# Multi2Meter.net
KiCad netlist of a schematic drawn in Altium Designer
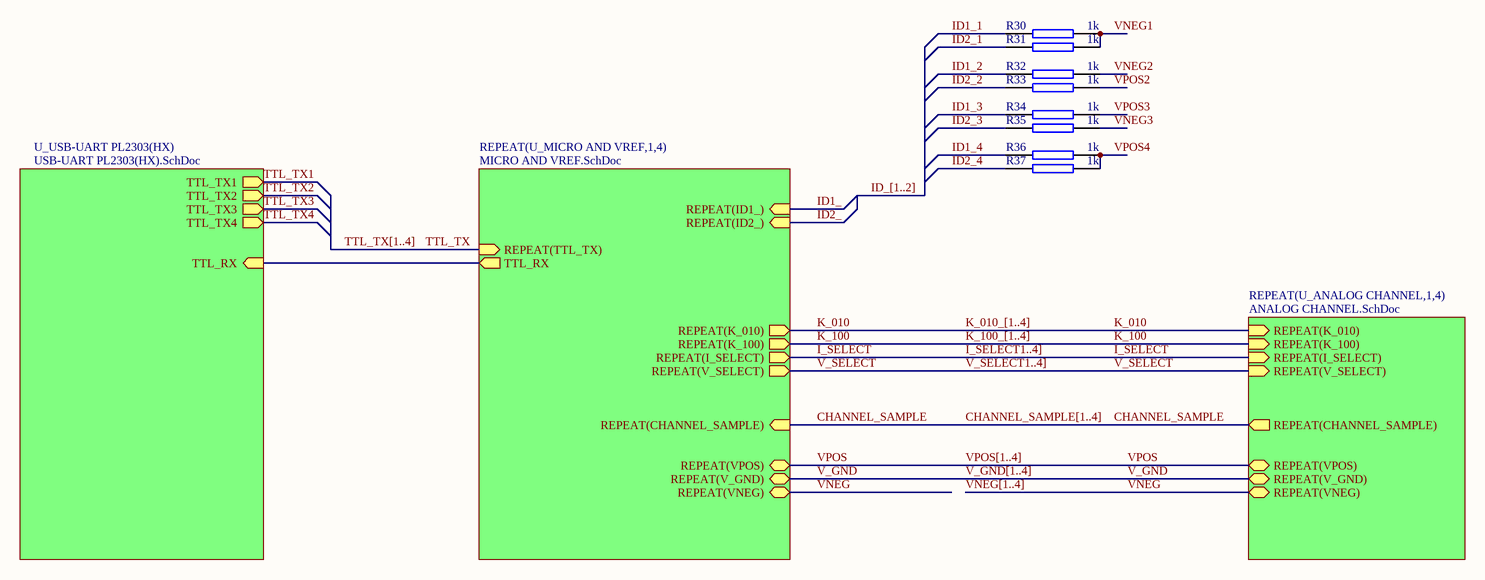
[diagram p0: Multi2Meter.SchDoc]

(export (version "E")
  (design (tool "Eeschema 10.0.6"))
  (components
    (comp (ref "R30")
      (value "1k")
      (footprint "RES (3D) - 0603")
      (description "RESISTOR SMD 0603")
      (libsource (lib "NASCO") (part "RES SMD 0603"))
    )
    (comp (ref "R31")
      (value "1k")
      (footprint "RES (3D) - 0603")
      (description "RESISTOR SMD 0603")
      (libsource (lib "NASCO") (part "RES SMD 0603"))
    )
    (comp (ref "R32")
      (value "1k")
      (footprint "RES (3D) - 0603")
      (description "RESISTOR SMD 0603")
      (libsource (lib "NASCO") (part "RES SMD 0603"))
    )
    (comp (ref "R33")
      (value "1k")
      (footprint "RES (3D) - 0603")
      (description "RESISTOR SMD 0603")
      (libsource (lib "NASCO") (part "RES SMD 0603"))
    )
    (comp (ref "R34")
      (value "1k")
      (footprint "RES (3D) - 0603")
      (description "RESISTOR SMD 0603")
      (libsource (lib "NASCO") (part "RES SMD 0603"))
    )
    (comp (ref "R35")
      (value "1k")
      (footprint "RES (3D) - 0603")
      (description "RESISTOR SMD 0603")
      (libsource (lib "NASCO") (part "RES SMD 0603"))
    )
    (comp (ref "R36")
      (value "1k")
      (footprint "RES (3D) - 0603")
      (description "RESISTOR SMD 0603")
      (libsource (lib "NASCO") (part "RES SMD 0603"))
    )
    (comp (ref "R37")
      (value "1k")
      (footprint "RES (3D) - 0603")
      (description "RESISTOR SMD 0603")
      (libsource (lib "NASCO") (part "RES SMD 0603"))
    )
  )
  (nets
    (net (code "26") (name "/ID1_1") (class "Default")
      (node (ref "R30") (pin "1") (pinfunction "1_1") (pintype "passive"))
    )
    (net (code "27") (name "/ID1_2") (class "Default")
      (node (ref "R32") (pin "1") (pinfunction "1_1") (pintype "passive"))
    )
    (net (code "28") (name "/ID1_3") (class "Default")
      (node (ref "R34") (pin "1") (pinfunction "1_1") (pintype "passive"))
    )
    (net (code "29") (name "/ID1_4") (class "Default")
      (node (ref "R36") (pin "1") (pinfunction "1_1") (pintype "passive"))
    )
    (net (code "31") (name "/ID2_1") (class "Default")
      (node (ref "R31") (pin "1") (pinfunction "1_1") (pintype "passive"))
    )
    (net (code "32") (name "/ID2_2") (class "Default")
      (node (ref "R33") (pin "1") (pinfunction "1_1") (pintype "passive"))
    )
    (net (code "33") (name "/ID2_3") (class "Default")
      (node (ref "R35") (pin "1") (pinfunction "1_1") (pintype "passive"))
    )
    (net (code "34") (name "/ID2_4") (class "Default")
      (node (ref "R37") (pin "1") (pinfunction "1_1") (pintype "passive"))
    )
    (net (code "49") (name "/VNEG1") (class "Default")
      (node (ref "R30") (pin "2") (pinfunction "2_2") (pintype "passive"))
      (node (ref "R31") (pin "2") (pinfunction "2_2") (pintype "passive"))
    )
    (net (code "50") (name "/VNEG2") (class "Default")
      (node (ref "R32") (pin "2") (pinfunction "2_2") (pintype "passive"))
    )
    (net (code "51") (name "/VNEG3") (class "Default")
      (node (ref "R35") (pin "2") (pinfunction "2_2") (pintype "passive"))
    )
    (net (code "54") (name "/VPOS2") (class "Default")
      (node (ref "R33") (pin "2") (pinfunction "2_2") (pintype "passive"))
    )
    (net (code "55") (name "/VPOS3") (class "Default")
      (node (ref "R34") (pin "2") (pinfunction "2_2") (pintype "passive"))
    )
    (net (code "56") (name "/VPOS4") (class "Default")
      (node (ref "R36") (pin "2") (pinfunction "2_2") (pintype "passive"))
      (node (ref "R37") (pin "2") (pinfunction "2_2") (pintype "passive"))
    )
  )
)
